# Sheet1.net
KiCad netlist of a schematic drawn in Altium Designer
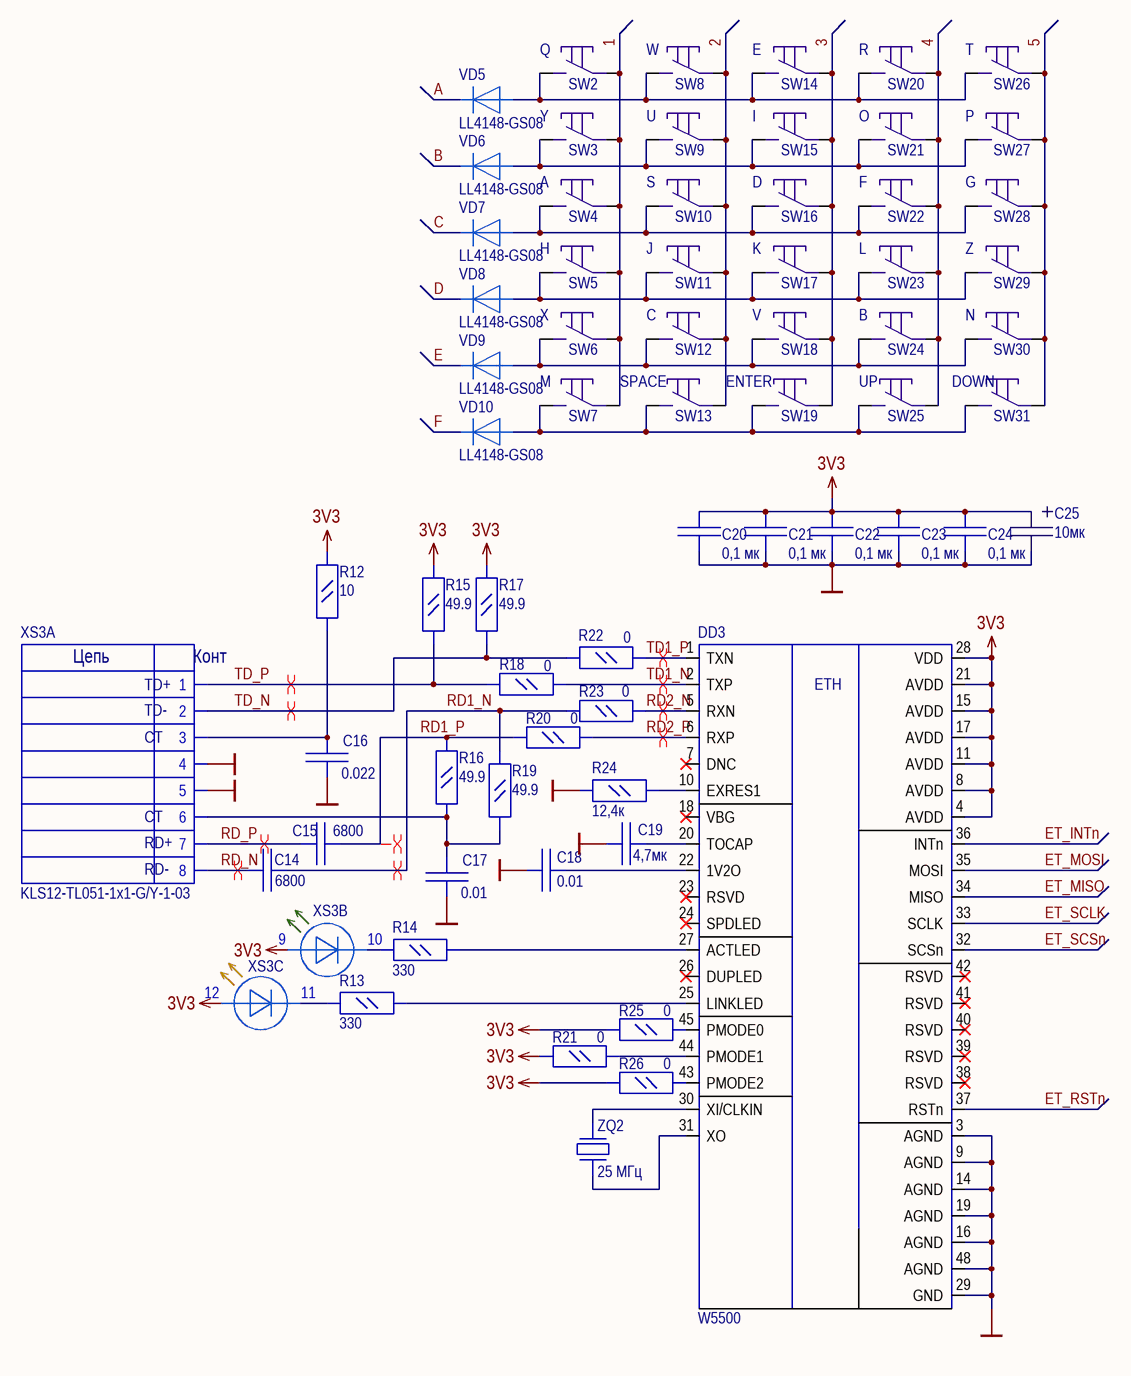
[diagram p0: Sheet1.SchDoc]

(export (version "E")
  (design (tool "Eeschema 10.0.6"))
  (components
    (comp (ref "C14") (value "6800") (footprint "C_0805") (libsource (lib "2.Capasitors") (part "C_0805")))
    (comp (ref "C15") (value "6800") (footprint "C_0805") (libsource (lib "2.Capasitors") (part "C_0805")))
    (comp (ref "C16") (value "0.022") (footprint "C_0805") (libsource (lib "2.Capasitors") (part "C_0805")))
    (comp (ref "C17") (value "0.01") (footprint "C_0805") (libsource (lib "2.Capasitors") (part "C_0805")))
    (comp (ref "C18") (value "0.01") (footprint "C_0805") (libsource (lib "2.Capasitors") (part "C_0805")))
    (comp (ref "C19") (value "4,7мк") (footprint "C_0805") (libsource (lib "2.Capasitors") (part "C_0805")))
    (comp (ref "C20") (value "0,1 мк") (footprint "C_0805") (libsource (lib "2.Capasitors") (part "C_0805")))
    (comp (ref "C21") (value "0,1 мк") (footprint "C_0805") (libsource (lib "2.Capasitors") (part "C_0805")))
    (comp (ref "C22") (value "0,1 мк") (footprint "C_0805") (libsource (lib "2.Capasitors") (part "C_0805")))
    (comp (ref "C23") (value "0,1 мк") (footprint "C_0805") (libsource (lib "2.Capasitors") (part "C_0805")))
    (comp (ref "C24") (value "0,1 мк") (footprint "C_0805") (libsource (lib "2.Capasitors") (part "C_0805")))
    (comp (ref "C25")
      (value "10мк")
      (footprint "D_CASE")
      (description "CAP TANT 10UF 10% 35V 2917")
      (fields (field (name "PART NUMBER") "T491D106K035AT") (field (name "MANUFACTURER") "KEMET"))
      (libsource (lib "Database_Lib") (part "Tantalum Capacitor"))
    )
    (comp (ref "DD3")
      (value "W5500")
      (footprint "LQFP48")
      (description "Hardwired TCP/IP embedded Ethernet controller")
      (libsource (lib "6.Chips") (part "W5500"))
    )
    (comp (ref "R12") (value "10") (footprint "R_0805") (libsource (lib "1.Resistors") (part "R_0805")))
    (comp (ref "R13") (value "330") (footprint "R_0805") (libsource (lib "1.Resistors") (part "R_0805")))
    (comp (ref "R14") (value "330") (footprint "R_0805") (libsource (lib "1.Resistors") (part "R_0805")))
    (comp (ref "R15") (value "49.9") (footprint "R_0805") (libsource (lib "1.Resistors") (part "R_0805")))
    (comp (ref "R16") (value "49.9") (footprint "R_0805") (libsource (lib "1.Resistors") (part "R_0805")))
    (comp (ref "R17") (value "49.9") (footprint "R_0805") (libsource (lib "1.Resistors") (part "R_0805")))
    (comp (ref "R18") (value "0") (footprint "R_0805") (libsource (lib "1.Resistors") (part "R_0805")))
    (comp (ref "R19") (value "49.9") (footprint "R_0805") (libsource (lib "1.Resistors") (part "R_0805")))
    (comp (ref "R20") (value "0") (footprint "R_0805") (libsource (lib "1.Resistors") (part "R_0805")))
    (comp (ref "R21") (value "0") (footprint "R_0805") (libsource (lib "1.Resistors") (part "R_0805")))
    (comp (ref "R22") (value "0") (footprint "R_0805") (libsource (lib "1.Resistors") (part "R_0805")))
    (comp (ref "R23") (value "0") (footprint "R_0805") (libsource (lib "1.Resistors") (part "R_0805")))
    (comp (ref "R24") (value "12,4к") (footprint "R_0805") (libsource (lib "1.Resistors") (part "R_0805")))
    (comp (ref "R25") (value "0") (footprint "R_0805") (libsource (lib "1.Resistors") (part "R_0805")))
    (comp (ref "R26") (value "0") (footprint "R_0805") (libsource (lib "1.Resistors") (part "R_0805")))
    (comp (ref "SW2")
      (value "KLS7-TS6604")
      (footprint "KLS7-TS6604-5.0-180-B")
      (libsource (lib "9.Commutation") (part "KLS7-TS6604"))
    )
    (comp (ref "SW3")
      (value "KLS7-TS6604")
      (footprint "KLS7-TS6604-5.0-180-B")
      (libsource (lib "9.Commutation") (part "KLS7-TS6604"))
    )
    (comp (ref "SW4")
      (value "KLS7-TS6604")
      (footprint "KLS7-TS6604-5.0-180-B")
      (libsource (lib "9.Commutation") (part "KLS7-TS6604"))
    )
    (comp (ref "SW5")
      (value "KLS7-TS6604")
      (footprint "KLS7-TS6604-5.0-180-B")
      (libsource (lib "9.Commutation") (part "KLS7-TS6604"))
    )
    (comp (ref "SW6")
      (value "KLS7-TS6604")
      (footprint "KLS7-TS6604-5.0-180-B")
      (libsource (lib "9.Commutation") (part "KLS7-TS6604"))
    )
    (comp (ref "SW7")
      (value "KLS7-TS6604")
      (footprint "KLS7-TS6604-5.0-180-B")
      (libsource (lib "9.Commutation") (part "KLS7-TS6604"))
    )
    (comp (ref "SW8")
      (value "KLS7-TS6604")
      (footprint "KLS7-TS6604-5.0-180-B")
      (libsource (lib "9.Commutation") (part "KLS7-TS6604"))
    )
    (comp (ref "SW9")
      (value "KLS7-TS6604")
      (footprint "KLS7-TS6604-5.0-180-B")
      (libsource (lib "9.Commutation") (part "KLS7-TS6604"))
    )
    (comp (ref "SW10")
      (value "KLS7-TS6604")
      (footprint "KLS7-TS6604-5.0-180-B")
      (libsource (lib "9.Commutation") (part "KLS7-TS6604"))
    )
    (comp (ref "SW11")
      (value "KLS7-TS6604")
      (footprint "KLS7-TS6604-5.0-180-B")
      (libsource (lib "9.Commutation") (part "KLS7-TS6604"))
    )
    (comp (ref "SW12")
      (value "KLS7-TS6604")
      (footprint "KLS7-TS6604-5.0-180-B")
      (libsource (lib "9.Commutation") (part "KLS7-TS6604"))
    )
    (comp (ref "SW13")
      (value "KLS7-TS6604")
      (footprint "KLS7-TS6604-5.0-180-B")
      (libsource (lib "9.Commutation") (part "KLS7-TS6604"))
    )
    (comp (ref "SW14")
      (value "KLS7-TS6604")
      (footprint "KLS7-TS6604-5.0-180-B")
      (libsource (lib "9.Commutation") (part "KLS7-TS6604"))
    )
    (comp (ref "SW15")
      (value "KLS7-TS6604")
      (footprint "KLS7-TS6604-5.0-180-B")
      (libsource (lib "9.Commutation") (part "KLS7-TS6604"))
    )
    (comp (ref "SW16")
      (value "KLS7-TS6604")
      (footprint "KLS7-TS6604-5.0-180-B")
      (libsource (lib "9.Commutation") (part "KLS7-TS6604"))
    )
    (comp (ref "SW17")
      (value "KLS7-TS6604")
      (footprint "KLS7-TS6604-5.0-180-B")
      (libsource (lib "9.Commutation") (part "KLS7-TS6604"))
    )
    (comp (ref "SW18")
      (value "KLS7-TS6604")
      (footprint "KLS7-TS6604-5.0-180-B")
      (libsource (lib "9.Commutation") (part "KLS7-TS6604"))
    )
    (comp (ref "SW19")
      (value "KLS7-TS6604")
      (footprint "KLS7-TS6604-5.0-180-B")
      (libsource (lib "9.Commutation") (part "KLS7-TS6604"))
    )
    (comp (ref "SW20")
      (value "KLS7-TS6604")
      (footprint "KLS7-TS6604-5.0-180-B")
      (libsource (lib "9.Commutation") (part "KLS7-TS6604"))
    )
    (comp (ref "SW21")
      (value "KLS7-TS6604")
      (footprint "KLS7-TS6604-5.0-180-B")
      (libsource (lib "9.Commutation") (part "KLS7-TS6604"))
    )
    (comp (ref "SW22")
      (value "KLS7-TS6604")
      (footprint "KLS7-TS6604-5.0-180-B")
      (libsource (lib "9.Commutation") (part "KLS7-TS6604"))
    )
    (comp (ref "SW23")
      (value "KLS7-TS6604")
      (footprint "KLS7-TS6604-5.0-180-B")
      (libsource (lib "9.Commutation") (part "KLS7-TS6604"))
    )
    (comp (ref "SW24")
      (value "KLS7-TS6604")
      (footprint "KLS7-TS6604-5.0-180-B")
      (libsource (lib "9.Commutation") (part "KLS7-TS6604"))
    )
    (comp (ref "SW25")
      (value "KLS7-TS6604")
      (footprint "KLS7-TS6604-5.0-180-B")
      (libsource (lib "9.Commutation") (part "KLS7-TS6604"))
    )
    (comp (ref "SW26")
      (value "KLS7-TS6604")
      (footprint "KLS7-TS6604-5.0-180-B")
      (libsource (lib "9.Commutation") (part "KLS7-TS6604"))
    )
    (comp (ref "SW27")
      (value "KLS7-TS6604")
      (footprint "KLS7-TS6604-5.0-180-B")
      (libsource (lib "9.Commutation") (part "KLS7-TS6604"))
    )
    (comp (ref "SW28")
      (value "KLS7-TS6604")
      (footprint "KLS7-TS6604-5.0-180-B")
      (libsource (lib "9.Commutation") (part "KLS7-TS6604"))
    )
    (comp (ref "SW29")
      (value "KLS7-TS6604")
      (footprint "KLS7-TS6604-5.0-180-B")
      (libsource (lib "9.Commutation") (part "KLS7-TS6604"))
    )
    (comp (ref "SW30")
      (value "KLS7-TS6604")
      (footprint "KLS7-TS6604-5.0-180-B")
      (libsource (lib "9.Commutation") (part "KLS7-TS6604"))
    )
    (comp (ref "SW31")
      (value "KLS7-TS6604")
      (footprint "KLS7-TS6604-5.0-180-B")
      (libsource (lib "9.Commutation") (part "KLS7-TS6604"))
    )
    (comp (ref "VD5")
      (value "LL4148-GS08")
      (footprint "SOD-80")
      (description "Диод")
      (libsource (lib "4.Diodes") (part "LL4148-GS08"))
    )
    (comp (ref "VD6")
      (value "LL4148-GS08")
      (footprint "SOD-80")
      (description "Диод")
      (libsource (lib "4.Diodes") (part "LL4148-GS08"))
    )
    (comp (ref "VD7")
      (value "LL4148-GS08")
      (footprint "SOD-80")
      (description "Диод")
      (libsource (lib "4.Diodes") (part "LL4148-GS08"))
    )
    (comp (ref "VD8")
      (value "LL4148-GS08")
      (footprint "SOD-80")
      (description "Диод")
      (libsource (lib "4.Diodes") (part "LL4148-GS08"))
    )
    (comp (ref "VD9")
      (value "LL4148-GS08")
      (footprint "SOD-80")
      (description "Диод")
      (libsource (lib "4.Diodes") (part "LL4148-GS08"))
    )
    (comp (ref "VD10")
      (value "LL4148-GS08")
      (footprint "SOD-80")
      (description "Диод")
      (libsource (lib "4.Diodes") (part "LL4148-GS08"))
    )
    (comp (ref "XS3")
      (value "KLS12-TL051-1x1-G/Y-1-03")
      (footprint "KLS12-TL051")
      (description "TJ16S-8P8C Разъем на плату 8-8 (RJ-45)")
      (libsource (lib "7.Connectors") (part "KLS12-TL051-1x1-G/Y-1-03"))
    )
    (comp (ref "ZQ2")
      (value "25 МГц")
      (footprint "MQ CRYSTAL")
      (libsource (lib "8.Resonarors") (part "MQ-25.000-18"))
    )
  )
  (nets
    (net (code "1") (name "/1") (class "Default")
      (node (ref "SW2") (pin "2") (pinfunction "2_2") (pintype "passive"))
      (node (ref "SW3") (pin "2") (pinfunction "2_2") (pintype "passive"))
      (node (ref "SW4") (pin "2") (pinfunction "2_2") (pintype "passive"))
      (node (ref "SW5") (pin "2") (pinfunction "2_2") (pintype "passive"))
      (node (ref "SW6") (pin "2") (pinfunction "2_2") (pintype "passive"))
      (node (ref "SW7") (pin "2") (pinfunction "2_2") (pintype "passive"))
    )
    (net (code "2") (name "/2") (class "Default")
      (node (ref "SW10") (pin "2") (pinfunction "2_2") (pintype "passive"))
      (node (ref "SW11") (pin "2") (pinfunction "2_2") (pintype "passive"))
      (node (ref "SW12") (pin "2") (pinfunction "2_2") (pintype "passive"))
      (node (ref "SW13") (pin "2") (pinfunction "2_2") (pintype "passive"))
      (node (ref "SW8") (pin "2") (pinfunction "2_2") (pintype "passive"))
      (node (ref "SW9") (pin "2") (pinfunction "2_2") (pintype "passive"))
    )
    (net (code "3") (name "/3") (class "Default")
      (node (ref "SW14") (pin "2") (pinfunction "2_2") (pintype "passive"))
      (node (ref "SW15") (pin "2") (pinfunction "2_2") (pintype "passive"))
      (node (ref "SW16") (pin "2") (pinfunction "2_2") (pintype "passive"))
      (node (ref "SW17") (pin "2") (pinfunction "2_2") (pintype "passive"))
      (node (ref "SW18") (pin "2") (pinfunction "2_2") (pintype "passive"))
      (node (ref "SW19") (pin "2") (pinfunction "2_2") (pintype "passive"))
    )
    (net (code "4") (name "/4") (class "Default")
      (node (ref "SW20") (pin "2") (pinfunction "2_2") (pintype "passive"))
      (node (ref "SW21") (pin "2") (pinfunction "2_2") (pintype "passive"))
      (node (ref "SW22") (pin "2") (pinfunction "2_2") (pintype "passive"))
      (node (ref "SW23") (pin "2") (pinfunction "2_2") (pintype "passive"))
      (node (ref "SW24") (pin "2") (pinfunction "2_2") (pintype "passive"))
      (node (ref "SW25") (pin "2") (pinfunction "2_2") (pintype "passive"))
    )
    (net (code "5") (name "/5") (class "Default")
      (node (ref "SW26") (pin "2") (pinfunction "2_2") (pintype "passive"))
      (node (ref "SW27") (pin "2") (pinfunction "2_2") (pintype "passive"))
      (node (ref "SW28") (pin "2") (pinfunction "2_2") (pintype "passive"))
      (node (ref "SW29") (pin "2") (pinfunction "2_2") (pintype "passive"))
      (node (ref "SW30") (pin "2") (pinfunction "2_2") (pintype "passive"))
      (node (ref "SW31") (pin "2") (pinfunction "2_2") (pintype "passive"))
    )
    (net (code "6") (name "/A") (class "Default")
      (node (ref "VD5") (pin "2") (pinfunction "2_2") (pintype "passive"))
    )
    (net (code "7") (name "/B") (class "Default")
      (node (ref "VD6") (pin "2") (pinfunction "2_2") (pintype "passive"))
    )
    (net (code "8") (name "/C") (class "Default")
      (node (ref "VD7") (pin "2") (pinfunction "2_2") (pintype "passive"))
    )
    (net (code "9") (name "/D") (class "Default")
      (node (ref "VD8") (pin "2") (pinfunction "2_2") (pintype "passive"))
    )
    (net (code "10") (name "/E") (class "Default")
      (node (ref "VD9") (pin "2") (pinfunction "2_2") (pintype "passive"))
    )
    (net (code "11") (name "/ET_INTn") (class "Default")
      (node (ref "DD3") (pin "36") (pinfunction "INTn_36") (pintype "passive"))
    )
    (net (code "12") (name "/ET_MISO") (class "Default")
      (node (ref "DD3") (pin "34") (pinfunction "MISO_34") (pintype "passive"))
    )
    (net (code "13") (name "/ET_MOSI") (class "Default")
      (node (ref "DD3") (pin "35") (pinfunction "MOSI_35") (pintype "passive"))
    )
    (net (code "14") (name "/ET_RSTn") (class "Default")
      (node (ref "DD3") (pin "37") (pinfunction "RSTn_37") (pintype "passive"))
    )
    (net (code "15") (name "/ET_SCLK") (class "Default")
      (node (ref "DD3") (pin "33") (pinfunction "SCLK_33") (pintype "passive"))
    )
    (net (code "16") (name "/ET_SCSn") (class "Default")
      (node (ref "DD3") (pin "32") (pinfunction "SCSn_32") (pintype "passive"))
    )
    (net (code "17") (name "/F") (class "Default")
      (node (ref "VD10") (pin "2") (pinfunction "2_2") (pintype "passive"))
    )
    (net (code "18") (name "/RD1_N") (class "Default")
      (node (ref "C14") (pin "1") (pinfunction "1_1") (pintype "passive"))
      (node (ref "R19") (pin "2") (pinfunction "2_2") (pintype "passive"))
      (node (ref "R23") (pin "1") (pinfunction "1_1") (pintype "passive"))
    )
    (net (code "19") (name "/RD1_P") (class "Default")
      (node (ref "C15") (pin "1") (pinfunction "1_1") (pintype "passive"))
      (node (ref "R16") (pin "2") (pinfunction "2_2") (pintype "passive"))
      (node (ref "R20") (pin "1") (pinfunction "1_1") (pintype "passive"))
    )
    (net (code "20") (name "/RD2_N") (class "Default")
      (node (ref "DD3") (pin "5") (pinfunction "RXN_5") (pintype "passive"))
      (node (ref "R23") (pin "2") (pinfunction "2_2") (pintype "passive"))
    )
    (net (code "21") (name "/RD2_P") (class "Default")
      (node (ref "DD3") (pin "6") (pinfunction "RXP_6") (pintype "passive"))
      (node (ref "R20") (pin "2") (pinfunction "2_2") (pintype "passive"))
    )
    (net (code "22") (name "/RD_N") (class "Default")
      (node (ref "C14") (pin "2") (pinfunction "2_2") (pintype "passive"))
      (node (ref "XS3") (pin "8") (pinfunction "8_8") (pintype "passive"))
    )
    (net (code "23") (name "/RD_P") (class "Default")
      (node (ref "C15") (pin "2") (pinfunction "2_2") (pintype "passive"))
      (node (ref "XS3") (pin "7") (pinfunction "7_7") (pintype "passive"))
    )
    (net (code "24") (name "/TD1_N") (class "Default")
      (node (ref "DD3") (pin "2") (pinfunction "TXP_2") (pintype "passive"))
      (node (ref "R18") (pin "2") (pinfunction "2_2") (pintype "passive"))
    )
    (net (code "25") (name "/TD1_P") (class "Default")
      (node (ref "DD3") (pin "1") (pinfunction "TXN_1") (pintype "passive"))
      (node (ref "R22") (pin "2") (pinfunction "2_2") (pintype "passive"))
    )
    (net (code "26") (name "/TD_N") (class "Default")
      (node (ref "R17") (pin "1") (pinfunction "1_1") (pintype "passive"))
      (node (ref "R22") (pin "1") (pinfunction "1_1") (pintype "passive"))
      (node (ref "XS3") (pin "2") (pinfunction "2_2") (pintype "passive"))
    )
    (net (code "27") (name "/TD_P") (class "Default")
      (node (ref "R15") (pin "1") (pinfunction "1_1") (pintype "passive"))
      (node (ref "R18") (pin "1") (pinfunction "1_1") (pintype "passive"))
      (node (ref "XS3") (pin "1") (pinfunction "1_1") (pintype "passive"))
    )
    (net (code "28") (name "3V3") (class "Default")
      (node (ref "C20") (pin "2") (pinfunction "2_2") (pintype "passive"))
      (node (ref "C21") (pin "2") (pinfunction "2_2") (pintype "passive"))
      (node (ref "C22") (pin "2") (pinfunction "2_2") (pintype "passive"))
      (node (ref "C23") (pin "2") (pinfunction "2_2") (pintype "passive"))
      (node (ref "C24") (pin "2") (pinfunction "2_2") (pintype "passive"))
      (node (ref "C25") (pin "1") (pinfunction "1_1") (pintype "passive"))
      (node (ref "DD3") (pin "11") (pinfunction "AVDD_11") (pintype "passive"))
      (node (ref "DD3") (pin "15") (pinfunction "AVDD_15") (pintype "passive"))
      (node (ref "DD3") (pin "17") (pinfunction "AVDD_17") (pintype "passive"))
      (node (ref "DD3") (pin "21") (pinfunction "AVDD_21") (pintype "passive"))
      (node (ref "DD3") (pin "28") (pinfunction "VDD_28") (pintype "passive"))
      (node (ref "DD3") (pin "4") (pinfunction "AVDD_4") (pintype "passive"))
      (node (ref "DD3") (pin "8") (pinfunction "AVDD_8") (pintype "passive"))
      (node (ref "R12") (pin "2") (pinfunction "2_2") (pintype "passive"))
      (node (ref "R15") (pin "2") (pinfunction "2_2") (pintype "passive"))
      (node (ref "R17") (pin "2") (pinfunction "2_2") (pintype "passive"))
      (node (ref "R21") (pin "1") (pinfunction "1_1") (pintype "passive"))
      (node (ref "R25") (pin "1") (pinfunction "1_1") (pintype "passive"))
      (node (ref "R26") (pin "1") (pinfunction "1_1") (pintype "passive"))
      (node (ref "XS3") (pin "12") (pinfunction "12_12") (pintype "passive"))
      (node (ref "XS3") (pin "9") (pinfunction "9_9") (pintype "passive"))
    )
    (net (code "29") (name "GND") (class "Default")
      (node (ref "C16") (pin "1") (pinfunction "1_1") (pintype "passive"))
      (node (ref "C17") (pin "1") (pinfunction "1_1") (pintype "passive"))
      (node (ref "C18") (pin "2") (pinfunction "2_2") (pintype "passive"))
      (node (ref "C19") (pin "2") (pinfunction "2_2") (pintype "passive"))
      (node (ref "C20") (pin "1") (pinfunction "1_1") (pintype "passive"))
      (node (ref "C21") (pin "1") (pinfunction "1_1") (pintype "passive"))
      (node (ref "C22") (pin "1") (pinfunction "1_1") (pintype "passive"))
      (node (ref "C23") (pin "1") (pinfunction "1_1") (pintype "passive"))
      (node (ref "C24") (pin "1") (pinfunction "1_1") (pintype "passive"))
      (node (ref "C25") (pin "2") (pinfunction "2_2") (pintype "passive"))
      (node (ref "DD3") (pin "14") (pinfunction "AGND_14") (pintype "passive"))
      (node (ref "DD3") (pin "16") (pinfunction "AGND_16") (pintype "passive"))
      (node (ref "DD3") (pin "19") (pinfunction "AGND_19") (pintype "passive"))
      (node (ref "DD3") (pin "29") (pinfunction "GND_29") (pintype "passive"))
      (node (ref "DD3") (pin "3") (pinfunction "AGND_3") (pintype "passive"))
      (node (ref "DD3") (pin "48") (pinfunction "AGND_48") (pintype "passive"))
      (node (ref "DD3") (pin "9") (pinfunction "AGND_9") (pintype "passive"))
      (node (ref "R24") (pin "1") (pinfunction "1_1") (pintype "passive"))
      (node (ref "XS3") (pin "4") (pinfunction "4_4") (pintype "passive"))
      (node (ref "XS3") (pin "5") (pinfunction "5_5") (pintype "passive"))
    )
    (net (code "30") (name "Net-(C16-Pad2)") (class "Default")
      (node (ref "C16") (pin "2") (pinfunction "2_2") (pintype "passive"))
      (node (ref "R12") (pin "1") (pinfunction "1_1") (pintype "passive"))
      (node (ref "XS3") (pin "3") (pinfunction "3_3") (pintype "passive"))
    )
    (net (code "31") (name "Net-(C17-Pad2)") (class "Default")
      (node (ref "C17") (pin "2") (pinfunction "2_2") (pintype "passive"))
      (node (ref "R16") (pin "1") (pinfunction "1_1") (pintype "passive"))
      (node (ref "R19") (pin "1") (pinfunction "1_1") (pintype "passive"))
      (node (ref "XS3") (pin "6") (pinfunction "6_6") (pintype "passive"))
    )
    (net (code "32") (name "Net-(DD3-1V2O)") (class "Default")
      (node (ref "C18") (pin "1") (pinfunction "1_1") (pintype "passive"))
      (node (ref "DD3") (pin "22") (pinfunction "1V2O_22") (pintype "passive"))
    )
    (net (code "33") (name "Net-(DD3-ACTLED)") (class "Default")
      (node (ref "DD3") (pin "27") (pinfunction "ACTLED_27") (pintype "passive"))
      (node (ref "R14") (pin "2") (pinfunction "2_2") (pintype "passive"))
    )
    (net (code "34") (name "Net-(DD3-EXRES1)") (class "Default")
      (node (ref "DD3") (pin "10") (pinfunction "EXRES1_10") (pintype "passive"))
      (node (ref "R24") (pin "2") (pinfunction "2_2") (pintype "passive"))
    )
    (net (code "35") (name "Net-(DD3-LINKLED)") (class "Default")
      (node (ref "DD3") (pin "25") (pinfunction "LINKLED_25") (pintype "passive"))
      (node (ref "R13") (pin "1") (pinfunction "1_1") (pintype "passive"))
    )
    (net (code "36") (name "Net-(DD3-PMODE0)") (class "Default")
      (node (ref "DD3") (pin "45") (pinfunction "PMODE0_45") (pintype "passive"))
      (node (ref "R25") (pin "2") (pinfunction "2_2") (pintype "passive"))
    )
    (net (code "37") (name "Net-(DD3-PMODE1)") (class "Default")
      (node (ref "DD3") (pin "44") (pinfunction "PMODE1_44") (pintype "passive"))
      (node (ref "R21") (pin "2") (pinfunction "2_2") (pintype "passive"))
    )
    (net (code "38") (name "Net-(DD3-PMODE2)") (class "Default")
      (node (ref "DD3") (pin "43") (pinfunction "PMODE2_43") (pintype "passive"))
      (node (ref "R26") (pin "2") (pinfunction "2_2") (pintype "passive"))
    )
    (net (code "39") (name "Net-(DD3-TOCAP)") (class "Default")
      (node (ref "C19") (pin "1") (pinfunction "1_1") (pintype "passive"))
      (node (ref "DD3") (pin "20") (pinfunction "TOCAP_20") (pintype "passive"))
    )
    (net (code "40") (name "Net-(DD3-XI{slash}CLKIN)") (class "Default")
      (node (ref "DD3") (pin "30") (pinfunction "XI/CLKIN_30") (pintype "passive"))
      (node (ref "ZQ2") (pin "1") (pinfunction "1_1") (pintype "passive"))
    )
    (net (code "41") (name "Net-(DD3-XO)") (class "Default")
      (node (ref "DD3") (pin "31") (pinfunction "XO_31") (pintype "passive"))
      (node (ref "ZQ2") (pin "3") (pinfunction "3_3") (pintype "passive"))
    )
    (net (code "42") (name "Net-(R13-Pad2)") (class "Default")
      (node (ref "R13") (pin "2") (pinfunction "2_2") (pintype "passive"))
      (node (ref "XS3") (pin "11") (pinfunction "11_11") (pintype "passive"))
    )
    (net (code "43") (name "Net-(R14-Pad1)") (class "Default")
      (node (ref "R14") (pin "1") (pinfunction "1_1") (pintype "passive"))
      (node (ref "XS3") (pin "10") (pinfunction "10_10") (pintype "passive"))
    )
    (net (code "44") (name "Net-(SW10-Pad1)") (class "Default")
      (node (ref "SW10") (pin "1") (pinfunction "1_1") (pintype "passive"))
      (node (ref "SW16") (pin "1") (pinfunction "1_1") (pintype "passive"))
      (node (ref "SW22") (pin "1") (pinfunction "1_1") (pintype "passive"))
      (node (ref "SW28") (pin "1") (pinfunction "1_1") (pintype "passive"))
      (node (ref "SW4") (pin "1") (pinfunction "1_1") (pintype "passive"))
      (node (ref "VD7") (pin "1") (pinfunction "1_1") (pintype "passive"))
    )
    (net (code "45") (name "Net-(SW11-Pad1)") (class "Default")
      (node (ref "SW11") (pin "1") (pinfunction "1_1") (pintype "passive"))
      (node (ref "SW17") (pin "1") (pinfunction "1_1") (pintype "passive"))
      (node (ref "SW23") (pin "1") (pinfunction "1_1") (pintype "passive"))
      (node (ref "SW29") (pin "1") (pinfunction "1_1") (pintype "passive"))
      (node (ref "SW5") (pin "1") (pinfunction "1_1") (pintype "passive"))
      (node (ref "VD8") (pin "1") (pinfunction "1_1") (pintype "passive"))
    )
    (net (code "46") (name "Net-(SW12-Pad1)") (class "Default")
      (node (ref "SW12") (pin "1") (pinfunction "1_1") (pintype "passive"))
      (node (ref "SW18") (pin "1") (pinfunction "1_1") (pintype "passive"))
      (node (ref "SW24") (pin "1") (pinfunction "1_1") (pintype "passive"))
      (node (ref "SW30") (pin "1") (pinfunction "1_1") (pintype "passive"))
      (node (ref "SW6") (pin "1") (pinfunction "1_1") (pintype "passive"))
      (node (ref "VD9") (pin "1") (pinfunction "1_1") (pintype "passive"))
    )
    (net (code "47") (name "Net-(SW13-Pad1)") (class "Default")
      (node (ref "SW13") (pin "1") (pinfunction "1_1") (pintype "passive"))
      (node (ref "SW19") (pin "1") (pinfunction "1_1") (pintype "passive"))
      (node (ref "SW25") (pin "1") (pinfunction "1_1") (pintype "passive"))
      (node (ref "SW31") (pin "1") (pinfunction "1_1") (pintype "passive"))
      (node (ref "SW7") (pin "1") (pinfunction "1_1") (pintype "passive"))
      (node (ref "VD10") (pin "1") (pinfunction "1_1") (pintype "passive"))
    )
    (net (code "48") (name "Net-(SW14-Pad1)") (class "Default")
      (node (ref "SW14") (pin "1") (pinfunction "1_1") (pintype "passive"))
      (node (ref "SW2") (pin "1") (pinfunction "1_1") (pintype "passive"))
      (node (ref "SW20") (pin "1") (pinfunction "1_1") (pintype "passive"))
      (node (ref "SW26") (pin "1") (pinfunction "1_1") (pintype "passive"))
      (node (ref "SW8") (pin "1") (pinfunction "1_1") (pintype "passive"))
      (node (ref "VD5") (pin "1") (pinfunction "1_1") (pintype "passive"))
    )
    (net (code "49") (name "Net-(SW15-Pad1)") (class "Default")
      (node (ref "SW15") (pin "1") (pinfunction "1_1") (pintype "passive"))
      (node (ref "SW21") (pin "1") (pinfunction "1_1") (pintype "passive"))
      (node (ref "SW27") (pin "1") (pinfunction "1_1") (pintype "passive"))
      (node (ref "SW3") (pin "1") (pinfunction "1_1") (pintype "passive"))
      (node (ref "SW9") (pin "1") (pinfunction "1_1") (pintype "passive"))
      (node (ref "VD6") (pin "1") (pinfunction "1_1") (pintype "passive"))
    )
    (net (code "50") (name "unconnected-(DD3-DNC-Pad7)") (class "Default")
      (node (ref "DD3") (pin "7") (pinfunction "DNC_7") (pintype "passive+no_connect"))
    )
    (net (code "51") (name "unconnected-(DD3-DUPLED-Pad26)") (class "Default")
      (node (ref "DD3") (pin "26") (pinfunction "DUPLED_26") (pintype "passive+no_connect"))
    )
    (net (code "52") (name "unconnected-(DD3-RSVD-Pad23)") (class "Default")
      (node (ref "DD3") (pin "23") (pinfunction "RSVD_23") (pintype "passive+no_connect"))
    )
    (net (code "53") (name "unconnected-(DD3-RSVD-Pad38)") (class "Default")
      (node (ref "DD3") (pin "38") (pinfunction "RSVD_38") (pintype "passive+no_connect"))
    )
    (net (code "54") (name "unconnected-(DD3-RSVD-Pad39)") (class "Default")
      (node (ref "DD3") (pin "39") (pinfunction "RSVD_39") (pintype "passive+no_connect"))
    )
    (net (code "55") (name "unconnected-(DD3-RSVD-Pad40)") (class "Default")
      (node (ref "DD3") (pin "40") (pinfunction "RSVD_40") (pintype "passive+no_connect"))
    )
    (net (code "56") (name "unconnected-(DD3-RSVD-Pad41)") (class "Default")
      (node (ref "DD3") (pin "41") (pinfunction "RSVD_41") (pintype "passive+no_connect"))
    )
    (net (code "57") (name "unconnected-(DD3-RSVD-Pad42)") (class "Default")
      (node (ref "DD3") (pin "42") (pinfunction "RSVD_42") (pintype "passive+no_connect"))
    )
    (net (code "58") (name "unconnected-(DD3-SPDLED-Pad24)") (class "Default")
      (node (ref "DD3") (pin "24") (pinfunction "SPDLED_24") (pintype "passive+no_connect"))
    )
    (net (code "59") (name "unconnected-(DD3-VBG-Pad18)") (class "Default")
      (node (ref "DD3") (pin "18") (pinfunction "VBG_18") (pintype "passive+no_connect"))
    )
  )
)
